# RHX-NYFK-SCH22V1_01.net
KiCad netlist of a schematic drawn in Altium Designer
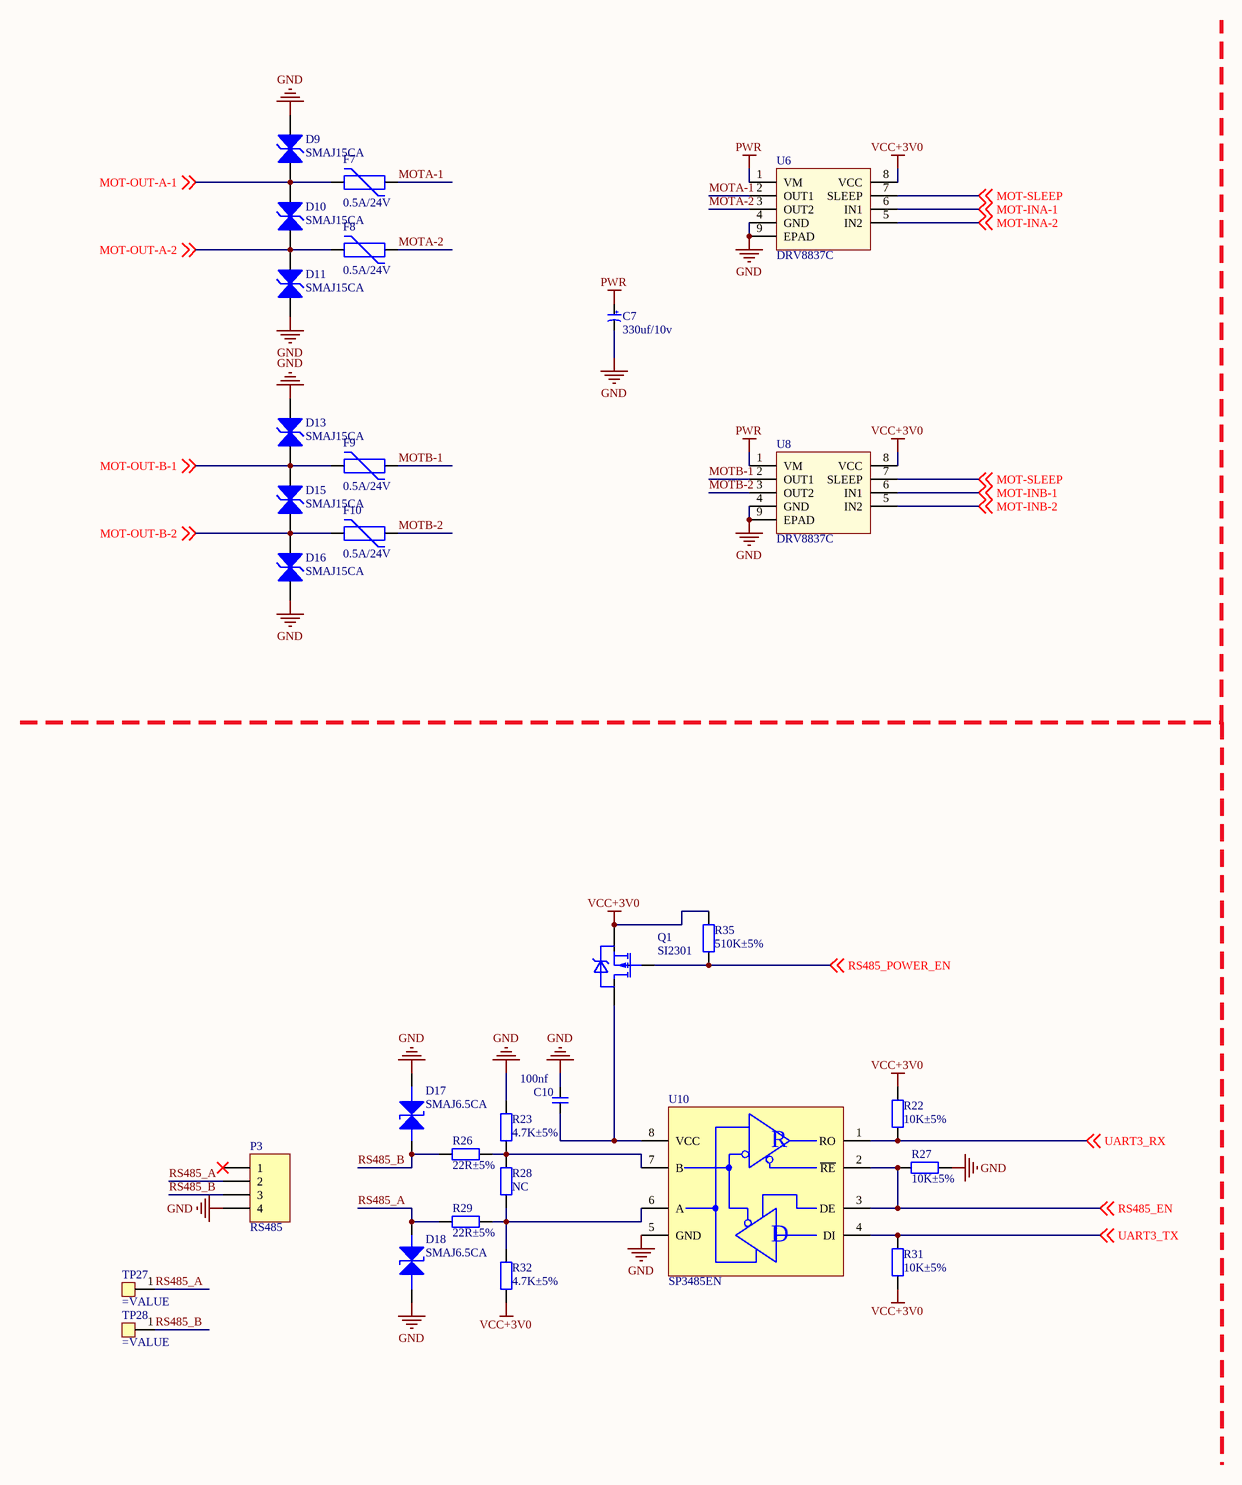
[diagram p0: RHX-NYFK-SCH22V1.01.SchDoc]

(export (version "E")
  (design (tool "Eeschema 10.0.6"))
  (components
    (comp (ref "C7")
      (value "330uf/10v")
      (footprint "CAP_2P_2R5_D6R3H11_W")
      (description "极性电容")
      (libsource (lib "瑞臻信息") (part "极性电容"))
    )
    (comp (ref "C10")
      (value "100nf")
      (footprint "c0402")
      (description "无极性电容")
      (libsource (lib "瑞臻信息") (part "无极性电容"))
    )
    (comp (ref "D9")
      (value "SMAJ15CA")
      (footprint "SMA_2P_2R8X4R6")
      (description "双向TVS管")
      (libsource (lib "瑞臻信息") (part "双向TVS管"))
    )
    (comp (ref "D10")
      (value "SMAJ15CA")
      (footprint "SMA_2P_2R8X4R6")
      (description "双向TVS管")
      (libsource (lib "瑞臻信息") (part "双向TVS管"))
    )
    (comp (ref "D11")
      (value "SMAJ15CA")
      (footprint "SMA_2P_2R8X4R6")
      (description "双向TVS管")
      (libsource (lib "瑞臻信息") (part "双向TVS管"))
    )
    (comp (ref "D13")
      (value "SMAJ15CA")
      (footprint "SMA_2P_2R8X4R6")
      (description "双向TVS管")
      (libsource (lib "瑞臻信息") (part "双向TVS管"))
    )
    (comp (ref "D15")
      (value "SMAJ15CA")
      (footprint "SMA_2P_2R8X4R6")
      (description "双向TVS管")
      (libsource (lib "瑞臻信息") (part "双向TVS管"))
    )
    (comp (ref "D16")
      (value "SMAJ15CA")
      (footprint "SMA_2P_2R8X4R6")
      (description "双向TVS管")
      (libsource (lib "瑞臻信息") (part "双向TVS管"))
    )
    (comp (ref "D17")
      (value "SMAJ6.5CA")
      (footprint "SMA_2P_2R8X4R6")
      (description "TVS管-SMBJ6.5CA-53.6A-单路-6.5Vrwm-8.3Vbr-600W-SMB")
      (libsource (lib "TM03-B_V01") (part "1.2.08.07.0014"))
    )
    (comp (ref "D18")
      (value "SMAJ6.5CA")
      (footprint "SMA_2P_2R8X4R6")
      (description "TVS管-SMBJ6.5CA-53.6A-单路-6.5Vrwm-8.3Vbr-600W-SMB")
      (libsource (lib "TM03-B_V01") (part "1.2.08.07.0014"))
    )
    (comp (ref "F7") (value "0.5A/24V") (footprint "FUSE1210") (libsource (lib "瑞臻信息") (part "PPTC")))
    (comp (ref "F8") (value "0.5A/24V") (footprint "FUSE1210") (libsource (lib "瑞臻信息") (part "PPTC")))
    (comp (ref "F9") (value "0.5A/24V") (footprint "FUSE1210") (libsource (lib "瑞臻信息") (part "PPTC")))
    (comp (ref "F10") (value "0.5A/24V") (footprint "FUSE1210") (libsource (lib "瑞臻信息") (part "PPTC")))
    (comp (ref "P3")
      (value "RS485")
      (footprint "HDR1X4")
      (description "Header, 4-Pin")
      (fields (field (name "PUBLISHER") "Altium Limited"))
      (libsource (lib "Miscellaneous Connectors") (part "Header 4"))
    )
    (comp (ref "Q1")
      (value "SI2301")
      (footprint "SOT23_3P_0R95_1R3X2R9")
      (description "P-MOS")
      (libsource (lib "瑞臻信息") (part "P-MOS"))
    )
    (comp (ref "R22")
      (value "10K±5%")
      (footprint "R0402")
      (description "电阻-10K±5%-1/16W-0402")
      (fields
        (field (name "PART NUMBER") "1.2.03.01.0012")
        (field (name "COMPONENTLINK1URL") "z:\\altiumdesigner\\规格书\\02原材料\\03电阻\\01普通电阻\\")
        (field (name "COMPONENTLINK2URL") "z:\\altiumdesigner\\规格书\\02原材料\\03电阻\\01普通电阻\\")
        (field (name "PUBLISHER") "徐永伟")
        (field (name "EDIT NOTE") "V1.0-创建-20161225-徐永伟")
        (field (name "COMPONENTLINK3URL") "z:\\altiumdesigner\\规格书\\02原材料\\03电阻\\01普通电阻\\")
        (field (name "COMPONENTLINK4URL") "z:\\altiumdesigner\\规格书\\02原材料\\03电阻\\01普通电阻\\")
      )
      (libsource (lib "") (part "普通电阻_1"))
    )
    (comp (ref "R23")
      (value "4.7K±5%")
      (footprint "R0402")
      (description "电阻-4.7K±5%-1/16W-0402")
      (fields
        (field (name "PART NUMBER") "1.2.03.01.0366")
        (field (name "COMPONENTLINK1URL") "z:\\altiumdesigner\\规格书\\02原材料\\03电阻\\01普通电阻\\")
        (field (name "COMPONENTLINK2URL") "z:\\altiumdesigner\\规格书\\02原材料\\03电阻\\01普通电阻\\")
        (field (name "PUBLISHER") "徐永伟")
        (field (name "EDIT NOTE") "V1.0-创建-20161225-徐永伟")
        (field (name "COMPONENTLINK3URL") "z:\\altiumdesigner\\规格书\\02原材料\\03电阻\\01普通电阻\\")
        (field (name "COMPONENTLINK4URL") "z:\\altiumdesigner\\规格书\\02原材料\\03电阻\\01普通电阻\\")
      )
      (libsource (lib "") (part "普通电阻_1"))
    )
    (comp (ref "R26")
      (value "22R±5%")
      (footprint "R0402")
      (description "电阻-4.7R±5%-1/16W-0402")
      (fields
        (field (name "PART NUMBER") "1.2.03.01.0573")
        (field (name "COMPONENTLINK1URL") "z:\\altiumdesigner\\规格书\\02原材料\\03电阻\\01普通电阻\\")
        (field (name "COMPONENTLINK2URL") "z:\\altiumdesigner\\规格书\\02原材料\\03电阻\\01普通电阻\\")
        (field (name "PUBLISHER") "徐永伟")
        (field (name "EDIT NOTE") "V1.0-创建-20161225-徐永伟")
        (field (name "COMPONENTLINK3URL") "z:\\altiumdesigner\\规格书\\02原材料\\03电阻\\01普通电阻\\")
        (field (name "COMPONENTLINK4URL") "z:\\altiumdesigner\\规格书\\02原材料\\03电阻\\01普通电阻\\")
      )
      (libsource (lib "檀木科技") (part "普通电阻"))
    )
    (comp (ref "R27")
      (value "10K±5%")
      (footprint "R0402")
      (description "电阻-10K±5%-1/16W-0402")
      (fields
        (field (name "PART NUMBER") "1.2.03.01.0012")
        (field (name "COMPONENTLINK1URL") "z:\\altiumdesigner\\规格书\\02原材料\\03电阻\\01普通电阻\\")
        (field (name "COMPONENTLINK2URL") "z:\\altiumdesigner\\规格书\\02原材料\\03电阻\\01普通电阻\\")
        (field (name "PUBLISHER") "徐永伟")
        (field (name "EDIT NOTE") "V1.0-创建-20161225-徐永伟")
        (field (name "COMPONENTLINK3URL") "z:\\altiumdesigner\\规格书\\02原材料\\03电阻\\01普通电阻\\")
        (field (name "COMPONENTLINK4URL") "z:\\altiumdesigner\\规格书\\02原材料\\03电阻\\01普通电阻\\")
      )
      (libsource (lib "") (part "普通电阻_2"))
    )
    (comp (ref "R28")
      (value "NC")
      (footprint "R0402")
      (description "电阻-10K±5%-1/16W-0402")
      (fields
        (field (name "PART NUMBER") "1.2.03.01.0012")
        (field (name "COMPONENTLINK1URL") "z:\\altiumdesigner\\规格书\\02原材料\\03电阻\\01普通电阻\\")
        (field (name "COMPONENTLINK2URL") "z:\\altiumdesigner\\规格书\\02原材料\\03电阻\\01普通电阻\\")
        (field (name "PUBLISHER") "徐永伟")
        (field (name "EDIT NOTE") "V1.0-创建-20161225-徐永伟")
        (field (name "COMPONENTLINK3URL") "z:\\altiumdesigner\\规格书\\02原材料\\03电阻\\01普通电阻\\")
        (field (name "COMPONENTLINK4URL") "z:\\altiumdesigner\\规格书\\02原材料\\03电阻\\01普通电阻\\")
      )
      (libsource (lib "") (part "普通电阻_1"))
    )
    (comp (ref "R29")
      (value "22R±5%")
      (footprint "R0402")
      (description "电阻-4.7R±5%-1/16W-0402")
      (fields
        (field (name "PART NUMBER") "1.2.03.01.0573")
        (field (name "COMPONENTLINK1URL") "z:\\altiumdesigner\\规格书\\02原材料\\03电阻\\01普通电阻\\")
        (field (name "COMPONENTLINK2URL") "z:\\altiumdesigner\\规格书\\02原材料\\03电阻\\01普通电阻\\")
        (field (name "PUBLISHER") "徐永伟")
        (field (name "EDIT NOTE") "V1.0-创建-20161225-徐永伟")
        (field (name "COMPONENTLINK3URL") "z:\\altiumdesigner\\规格书\\02原材料\\03电阻\\01普通电阻\\")
        (field (name "COMPONENTLINK4URL") "z:\\altiumdesigner\\规格书\\02原材料\\03电阻\\01普通电阻\\")
      )
      (libsource (lib "檀木科技") (part "普通电阻"))
    )
    (comp (ref "R31")
      (value "10K±5%")
      (footprint "R0402")
      (description "电阻-10K±5%-1/16W-0402")
      (fields
        (field (name "PART NUMBER") "1.2.03.01.0012")
        (field (name "COMPONENTLINK1URL") "z:\\altiumdesigner\\规格书\\02原材料\\03电阻\\01普通电阻\\")
        (field (name "COMPONENTLINK2URL") "z:\\altiumdesigner\\规格书\\02原材料\\03电阻\\01普通电阻\\")
        (field (name "PUBLISHER") "徐永伟")
        (field (name "EDIT NOTE") "V1.0-创建-20161225-徐永伟")
        (field (name "COMPONENTLINK3URL") "z:\\altiumdesigner\\规格书\\02原材料\\03电阻\\01普通电阻\\")
        (field (name "COMPONENTLINK4URL") "z:\\altiumdesigner\\规格书\\02原材料\\03电阻\\01普通电阻\\")
      )
      (libsource (lib "") (part "普通电阻_1"))
    )
    (comp (ref "R32")
      (value "4.7K±5%")
      (footprint "R0402")
      (description "电阻-4.7K±5%-1/16W-0402")
      (fields
        (field (name "PART NUMBER") "1.2.03.01.0366")
        (field (name "COMPONENTLINK1URL") "z:\\altiumdesigner\\规格书\\02原材料\\03电阻\\01普通电阻\\")
        (field (name "COMPONENTLINK2URL") "z:\\altiumdesigner\\规格书\\02原材料\\03电阻\\01普通电阻\\")
        (field (name "PUBLISHER") "徐永伟")
        (field (name "EDIT NOTE") "V1.0-创建-20161225-徐永伟")
        (field (name "COMPONENTLINK3URL") "z:\\altiumdesigner\\规格书\\02原材料\\03电阻\\01普通电阻\\")
        (field (name "COMPONENTLINK4URL") "z:\\altiumdesigner\\规格书\\02原材料\\03电阻\\01普通电阻\\")
      )
      (libsource (lib "") (part "普通电阻_1"))
    )
    (comp (ref "R35")
      (value "510K±5%")
      (footprint "R0402")
      (description "电阻-10K±5%-1/16W-0402")
      (fields
        (field (name "PART NUMBER") "1.2.03.01.0012")
        (field (name "COMPONENTLINK1URL") "z:\\altiumdesigner\\规格书\\02原材料\\03电阻\\01普通电阻\\")
        (field (name "COMPONENTLINK2URL") "z:\\altiumdesigner\\规格书\\02原材料\\03电阻\\01普通电阻\\")
        (field (name "PUBLISHER") "徐永伟")
        (field (name "EDIT NOTE") "V1.0-创建-20161225-徐永伟")
        (field (name "COMPONENTLINK3URL") "z:\\altiumdesigner\\规格书\\02原材料\\03电阻\\01普通电阻\\")
        (field (name "COMPONENTLINK4URL") "z:\\altiumdesigner\\规格书\\02原材料\\03电阻\\01普通电阻\\")
      )
      (libsource (lib "") (part "普通电阻_3"))
    )
    (comp (ref "TP27")
      (value "~")
      (footprint "TP_D1R25")
      (description "测试点")
      (libsource (lib "瑞臻信息") (part "Test_Point"))
    )
    (comp (ref "TP28")
      (value "~")
      (footprint "TP_D1R25")
      (description "测试点")
      (libsource (lib "瑞臻信息") (part "Test_Point"))
    )
    (comp (ref "U6")
      (value "DRV8837C")
      (footprint "TDFN_8P_0R5_2R0X2R0_P")
      (libsource (lib "瑞臻信息") (part "DRV8837C"))
    )
    (comp (ref "U8")
      (value "DRV8837C")
      (footprint "TDFN_8P_0R5_2R0X2R0_P")
      (libsource (lib "瑞臻信息") (part "DRV8837C"))
    )
    (comp (ref "U10")
      (value "SP3485EN")
      (footprint "SOP_8P_1R27_3R9X4R9")
      (description "RS485收发器-SP3485EN-支持485收发-SOP8")
      (fields
        (field (name "PART NUMBER") "1.2.18.09.0173")
        (field (name "COMPONENTLINK1URL") "Z:\\AltiumDesigner\\规格书\\02原材料\\18集成电路\\09接口芯片\\SP3485EN.pdf")
        (field (name "PUBLISHER") "徐永伟")
        (field (name "EDIT NOTE") "V1.0-创建-20170122-徐永伟")
      )
      (libsource (lib "檀木科技") (part "SP3485"))
    )
  )
  (nets
    (net (code "1") (name "/MOTA-1") (class "Default")
      (node (ref "F7") (pin "2") (pinfunction "2_2") (pintype "passive"))
      (node (ref "U6") (pin "2") (pinfunction "OUT1_2") (pintype "passive"))
    )
    (net (code "2") (name "/MOTA-2") (class "Default")
      (node (ref "F8") (pin "2") (pinfunction "2_2") (pintype "passive"))
      (node (ref "U6") (pin "3") (pinfunction "OUT2_3") (pintype "passive"))
    )
    (net (code "3") (name "/MOTB-1") (class "Default")
      (node (ref "F9") (pin "2") (pinfunction "2_2") (pintype "passive"))
      (node (ref "U8") (pin "2") (pinfunction "OUT1_2") (pintype "passive"))
    )
    (net (code "4") (name "/MOTB-2") (class "Default")
      (node (ref "F10") (pin "2") (pinfunction "2_2") (pintype "passive"))
      (node (ref "U8") (pin "3") (pinfunction "OUT2_3") (pintype "passive"))
    )
    (net (code "5") (name "/RS485_A") (class "Default")
      (node (ref "D18") (pin "1") (pinfunction "A_1") (pintype "passive"))
      (node (ref "P3") (pin "2") (pinfunction "2_2") (pintype "passive"))
      (node (ref "R29") (pin "2") (pinfunction "2_2") (pintype "passive"))
      (node (ref "TP27") (pin "1") (pinfunction "1_1") (pintype "passive"))
    )
    (net (code "6") (name "/RS485_B") (class "Default")
      (node (ref "D17") (pin "1") (pinfunction "A_1") (pintype "passive"))
      (node (ref "P3") (pin "3") (pinfunction "3_3") (pintype "passive"))
      (node (ref "R26") (pin "2") (pinfunction "2_2") (pintype "passive"))
      (node (ref "TP28") (pin "1") (pinfunction "1_1") (pintype "passive"))
    )
    (net (code "7") (name "GND") (class "Default")
      (node (ref "C10") (pin "2") (pinfunction "2_2") (pintype "passive"))
      (node (ref "C7") (pin "2") (pinfunction "2_2") (pintype "passive"))
      (node (ref "D11") (pin "1") (pinfunction "A_1") (pintype "passive"))
      (node (ref "D13") (pin "2") (pinfunction "K_2") (pintype "passive"))
      (node (ref "D16") (pin "1") (pinfunction "A_1") (pintype "passive"))
      (node (ref "D17") (pin "2") (pinfunction "K_2") (pintype "passive"))
      (node (ref "D18") (pin "2") (pinfunction "K_2") (pintype "passive"))
      (node (ref "D9") (pin "2") (pinfunction "K_2") (pintype "passive"))
      (node (ref "P3") (pin "4") (pinfunction "4_4") (pintype "passive"))
      (node (ref "R23") (pin "2") (pinfunction "2_2") (pintype "passive"))
      (node (ref "R27") (pin "2") (pinfunction "2_2") (pintype "passive"))
      (node (ref "U10") (pin "5") (pinfunction "GND_5") (pintype "passive"))
      (node (ref "U6") (pin "4") (pinfunction "GND_4") (pintype "passive"))
      (node (ref "U6") (pin "9") (pinfunction "EPAD_9") (pintype "passive"))
      (node (ref "U8") (pin "4") (pinfunction "GND_4") (pintype "passive"))
      (node (ref "U8") (pin "9") (pinfunction "EPAD_9") (pintype "passive"))
    )
    (net (code "8") (name "MOT-INA-1") (class "Default")
      (node (ref "U6") (pin "6") (pinfunction "IN1_6") (pintype "passive"))
    )
    (net (code "9") (name "MOT-INA-2") (class "Default")
      (node (ref "U6") (pin "5") (pinfunction "IN2_5") (pintype "passive"))
    )
    (net (code "10") (name "MOT-INB-1") (class "Default")
      (node (ref "U8") (pin "6") (pinfunction "IN1_6") (pintype "passive"))
    )
    (net (code "11") (name "MOT-INB-2") (class "Default")
      (node (ref "U8") (pin "5") (pinfunction "IN2_5") (pintype "passive"))
    )
    (net (code "12") (name "MOT-OUT-A-1") (class "Default")
      (node (ref "D10") (pin "2") (pinfunction "K_2") (pintype "passive"))
      (node (ref "D9") (pin "1") (pinfunction "A_1") (pintype "passive"))
      (node (ref "F7") (pin "1") (pinfunction "1_1") (pintype "passive"))
    )
    (net (code "13") (name "MOT-OUT-A-2") (class "Default")
      (node (ref "D10") (pin "1") (pinfunction "A_1") (pintype "passive"))
      (node (ref "D11") (pin "2") (pinfunction "K_2") (pintype "passive"))
      (node (ref "F8") (pin "1") (pinfunction "1_1") (pintype "passive"))
    )
    (net (code "14") (name "MOT-OUT-B-1") (class "Default")
      (node (ref "D13") (pin "1") (pinfunction "A_1") (pintype "passive"))
      (node (ref "D15") (pin "2") (pinfunction "K_2") (pintype "passive"))
      (node (ref "F9") (pin "1") (pinfunction "1_1") (pintype "passive"))
    )
    (net (code "15") (name "MOT-OUT-B-2") (class "Default")
      (node (ref "D15") (pin "1") (pinfunction "A_1") (pintype "passive"))
      (node (ref "D16") (pin "2") (pinfunction "K_2") (pintype "passive"))
      (node (ref "F10") (pin "1") (pinfunction "1_1") (pintype "passive"))
    )
    (net (code "16") (name "MOT-SLEEP") (class "Default")
      (node (ref "U6") (pin "7") (pinfunction "SLEEP_7") (pintype "passive"))
      (node (ref "U8") (pin "7") (pinfunction "SLEEP_7") (pintype "passive"))
    )
    (net (code "17") (name "Net-(Q1-D)") (class "Default")
      (node (ref "C10") (pin "1") (pinfunction "1_1") (pintype "passive"))
      (node (ref "Q1") (pin "3") (pinfunction "D_3") (pintype "passive"))
      (node (ref "U10") (pin "8") (pinfunction "VCC_8") (pintype "passive"))
    )
    (net (code "18") (name "Net-(U10-A)") (class "Default")
      (node (ref "R28") (pin "1") (pinfunction "1_1") (pintype "passive"))
      (node (ref "R29") (pin "1") (pinfunction "1_1") (pintype "passive"))
      (node (ref "R32") (pin "2") (pinfunction "2_2") (pintype "passive"))
      (node (ref "U10") (pin "6") (pinfunction "A_6") (pintype "passive"))
    )
    (net (code "19") (name "Net-(U10-B)") (class "Default")
      (node (ref "R23") (pin "1") (pinfunction "1_1") (pintype "passive"))
      (node (ref "R26") (pin "1") (pinfunction "1_1") (pintype "passive"))
      (node (ref "R28") (pin "2") (pinfunction "2_2") (pintype "passive"))
      (node (ref "U10") (pin "7") (pinfunction "B_7") (pintype "passive"))
    )
    (net (code "20") (name "PWR") (class "Default")
      (node (ref "C7") (pin "1") (pinfunction "1_1") (pintype "passive"))
      (node (ref "U6") (pin "1") (pinfunction "VM_1") (pintype "passive"))
      (node (ref "U8") (pin "1") (pinfunction "VM_1") (pintype "passive"))
    )
    (net (code "21") (name "RS485_EN") (class "Default")
      (node (ref "R27") (pin "1") (pinfunction "1_1") (pintype "passive"))
      (node (ref "U10") (pin "2") (pinfunction "~{RE}_2") (pintype "passive"))
      (node (ref "U10") (pin "3") (pinfunction "DE_3") (pintype "passive"))
    )
    (net (code "22") (name "RS485_POWER_EN") (class "Default")
      (node (ref "Q1") (pin "1") (pinfunction "G_1") (pintype "passive"))
      (node (ref "R35") (pin "2") (pinfunction "2_2") (pintype "passive"))
    )
    (net (code "23") (name "UART3_RX") (class "Default")
      (node (ref "R22") (pin "1") (pinfunction "1_1") (pintype "passive"))
      (node (ref "U10") (pin "1") (pinfunction "RO_1") (pintype "passive"))
    )
    (net (code "24") (name "UART3_TX") (class "Default")
      (node (ref "R31") (pin "2") (pinfunction "2_2") (pintype "passive"))
      (node (ref "U10") (pin "4") (pinfunction "DI_4") (pintype "passive"))
    )
    (net (code "25") (name "VCC+3V0") (class "Default")
      (node (ref "Q1") (pin "2") (pinfunction "S_2") (pintype "passive"))
      (node (ref "R22") (pin "2") (pinfunction "2_2") (pintype "passive"))
      (node (ref "R31") (pin "1") (pinfunction "1_1") (pintype "passive"))
      (node (ref "R32") (pin "1") (pinfunction "1_1") (pintype "passive"))
      (node (ref "R35") (pin "1") (pinfunction "1_1") (pintype "passive"))
      (node (ref "U6") (pin "8") (pinfunction "VCC_8") (pintype "passive"))
      (node (ref "U8") (pin "8") (pinfunction "VCC_8") (pintype "passive"))
    )
    (net (code "26") (name "unconnected-(P3-Pad1)") (class "Default")
      (node (ref "P3") (pin "1") (pinfunction "1_1") (pintype "passive+no_connect"))
    )
  )
)
